# Attenuverting_mixer_mutes.net
KiCad netlist of a schematic drawn in EAGLE
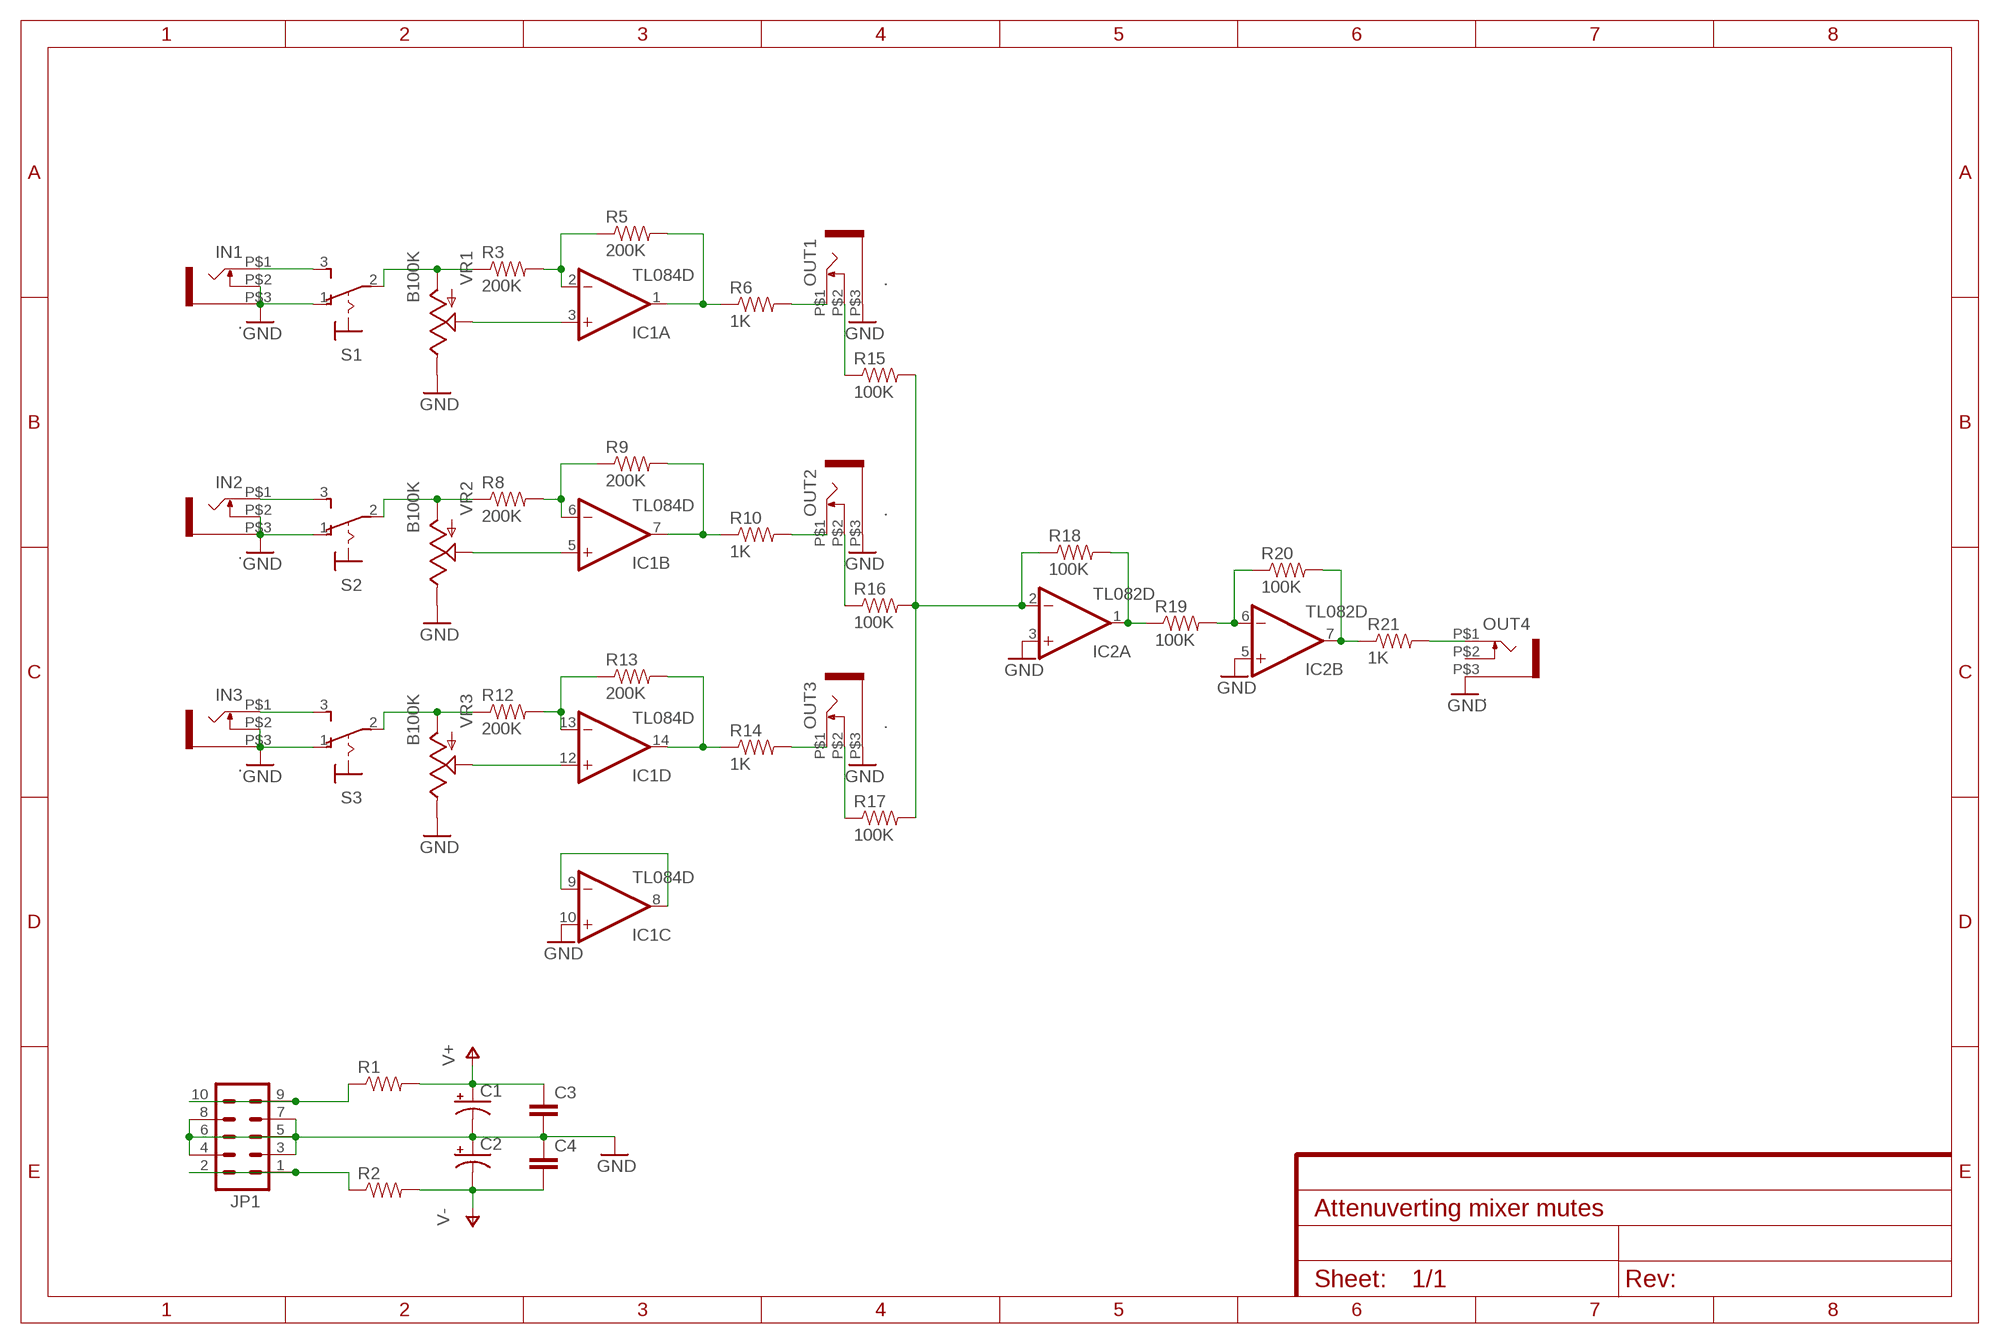
[diagram p0: schematic, sheet 1]

(export (version "E")
  (design (tool "Eeschema 10.0.6"))
  (components
    (comp (ref "C1")
      (value "CAP_POLD")
      (footprint "eagle-import:PANASONIC_D")
      (libsource (lib "eagle-import") (part "CAP_POLD"))
    )
    (comp (ref "C2")
      (value "CAP_POLD")
      (footprint "eagle-import:PANASONIC_D")
      (libsource (lib "eagle-import") (part "CAP_POLD"))
    )
    (comp (ref "C3")
      (value "CAP0603-CAP")
      (footprint "eagle-import:0603-CAP")
      (libsource (lib "eagle-import") (part "CAP0603-CAP"))
    )
    (comp (ref "C4")
      (value "CAP0603-CAP")
      (footprint "eagle-import:0603-CAP")
      (libsource (lib "eagle-import") (part "CAP0603-CAP"))
    )
    (comp (ref "IC1")
      (value "TL084D")
      (footprint "eagle-import:SO14")
      (libsource (lib "eagle-import") (part "TL084D"))
    )
    (comp (ref "IC2")
      (value "TL082D")
      (footprint "eagle-import:SO08")
      (libsource (lib "eagle-import") (part "TL082D"))
    )
    (comp (ref "IN1")
      (value ".")
      (footprint "eagle-import:WQP-PJ301M-12_JACK")
      (libsource (lib "eagle-import") (part "WQP-PJ301M-12_JACK"))
    )
    (comp (ref "IN2")
      (value ".")
      (footprint "eagle-import:WQP-PJ301M-12_JACK")
      (libsource (lib "eagle-import") (part "WQP-PJ301M-12_JACK"))
    )
    (comp (ref "IN3")
      (value ".")
      (footprint "eagle-import:WQP-PJ301M-12_JACK")
      (libsource (lib "eagle-import") (part "WQP-PJ301M-12_JACK"))
    )
    (comp (ref "JP1")
      (value "M05X2PTH")
      (footprint "eagle-import:AVR_ICSP")
      (libsource (lib "eagle-import") (part "M05X2PTH"))
    )
    (comp (ref "OUT1")
      (value ".")
      (footprint "eagle-import:WQP-PJ301M-12_JACK")
      (libsource (lib "eagle-import") (part "WQP-PJ301M-12_JACK"))
    )
    (comp (ref "OUT2")
      (value ".")
      (footprint "eagle-import:WQP-PJ301M-12_JACK")
      (libsource (lib "eagle-import") (part "WQP-PJ301M-12_JACK"))
    )
    (comp (ref "OUT3")
      (value ".")
      (footprint "eagle-import:WQP-PJ301M-12_JACK")
      (libsource (lib "eagle-import") (part "WQP-PJ301M-12_JACK"))
    )
    (comp (ref "OUT4")
      (value ".")
      (footprint "eagle-import:WQP-PJ301M-12_JACK")
      (libsource (lib "eagle-import") (part "WQP-PJ301M-12_JACK"))
    )
    (comp (ref "R1")
      (value "RESISTOR0805-RES")
      (footprint "eagle-import:0805")
      (libsource (lib "eagle-import") (part "SparkFun-Resistors_RESISTOR0805-RES"))
    )
    (comp (ref "R2")
      (value "RESISTOR0805-RES")
      (footprint "eagle-import:0805")
      (libsource (lib "eagle-import") (part "SparkFun-Resistors_RESISTOR0805-RES"))
    )
    (comp (ref "R3")
      (value "200K")
      (footprint "eagle-import:0603-RES")
      (libsource (lib "eagle-import") (part "RESISTOR0603-RES"))
    )
    (comp (ref "R5")
      (value "200K")
      (footprint "eagle-import:0603-RES")
      (libsource (lib "eagle-import") (part "RESISTOR0603-RES"))
    )
    (comp (ref "R6")
      (value "1K")
      (footprint "eagle-import:0603-RES")
      (libsource (lib "eagle-import") (part "RESISTOR0603-RES"))
    )
    (comp (ref "R8")
      (value "200K")
      (footprint "eagle-import:0603-RES")
      (libsource (lib "eagle-import") (part "RESISTOR0603-RES"))
    )
    (comp (ref "R9")
      (value "200K")
      (footprint "eagle-import:0603-RES")
      (libsource (lib "eagle-import") (part "RESISTOR0603-RES"))
    )
    (comp (ref "R10")
      (value "1K")
      (footprint "eagle-import:0603-RES")
      (libsource (lib "eagle-import") (part "RESISTOR0603-RES"))
    )
    (comp (ref "R12")
      (value "200K")
      (footprint "eagle-import:0603-RES")
      (libsource (lib "eagle-import") (part "RESISTOR0603-RES"))
    )
    (comp (ref "R13")
      (value "200K")
      (footprint "eagle-import:0603-RES")
      (libsource (lib "eagle-import") (part "RESISTOR0603-RES"))
    )
    (comp (ref "R14")
      (value "1K")
      (footprint "eagle-import:0603-RES")
      (libsource (lib "eagle-import") (part "RESISTOR0603-RES"))
    )
    (comp (ref "R15")
      (value "100K")
      (footprint "eagle-import:0603-RES")
      (libsource (lib "eagle-import") (part "RESISTOR0603-RES"))
    )
    (comp (ref "R16")
      (value "100K")
      (footprint "eagle-import:0603-RES")
      (libsource (lib "eagle-import") (part "RESISTOR0603-RES"))
    )
    (comp (ref "R17")
      (value "100K")
      (footprint "eagle-import:0603-RES")
      (libsource (lib "eagle-import") (part "RESISTOR0603-RES"))
    )
    (comp (ref "R18")
      (value "100K")
      (footprint "eagle-import:0603-RES")
      (libsource (lib "eagle-import") (part "RESISTOR0603-RES"))
    )
    (comp (ref "R19")
      (value "100K")
      (footprint "eagle-import:0603-RES")
      (libsource (lib "eagle-import") (part "RESISTOR0603-RES"))
    )
    (comp (ref "R20")
      (value "100K")
      (footprint "eagle-import:0603-RES")
      (libsource (lib "eagle-import") (part "RESISTOR0603-RES"))
    )
    (comp (ref "R21")
      (value "1K")
      (footprint "eagle-import:0603-RES")
      (libsource (lib "eagle-import") (part "RESISTOR0603-RES"))
    )
    (comp (ref "S1")
      (value "M9040P")
      (footprint "eagle-import:M9040P")
      (libsource (lib "eagle-import") (part "M9040P"))
    )
    (comp (ref "S2")
      (value "M9040P")
      (footprint "eagle-import:M9040P")
      (libsource (lib "eagle-import") (part "M9040P"))
    )
    (comp (ref "S3")
      (value "M9040P")
      (footprint "eagle-import:M9040P")
      (libsource (lib "eagle-import") (part "M9040P"))
    )
    (comp (ref "VR1")
      (value "B100K")
      (footprint "eagle-import:ALPS_POT")
      (libsource (lib "eagle-import") (part "POT"))
    )
    (comp (ref "VR2")
      (value "B100K")
      (footprint "eagle-import:ALPS_POT")
      (libsource (lib "eagle-import") (part "POT"))
    )
    (comp (ref "VR3")
      (value "B100K")
      (footprint "eagle-import:ALPS_POT")
      (libsource (lib "eagle-import") (part "POT"))
    )
  )
  (nets
    (net (code "1") (name "GND") (class "Default")
      (node (ref "C1") (pin "-") (pinfunction "-_-") (pintype "passive"))
      (node (ref "C2") (pin "+") (pinfunction "+_+") (pintype "passive"))
      (node (ref "C3") (pin "2") (pinfunction "2_2") (pintype "passive"))
      (node (ref "C4") (pin "1") (pinfunction "1_1") (pintype "passive"))
      (node (ref "IC1") (pin "10") (pinfunction "+IN_10") (pintype "input"))
      (node (ref "IC2") (pin "3") (pinfunction "+IN_3") (pintype "input"))
      (node (ref "IC2") (pin "5") (pinfunction "+IN_5") (pintype "input"))
      (node (ref "IN1") (pin "P$2") (pinfunction "3_P$2") (pintype "passive"))
      (node (ref "IN1") (pin "P$3") (pinfunction "1_P$3") (pintype "passive"))
      (node (ref "IN2") (pin "P$2") (pinfunction "3_P$2") (pintype "passive"))
      (node (ref "IN2") (pin "P$3") (pinfunction "1_P$3") (pintype "passive"))
      (node (ref "IN3") (pin "P$2") (pinfunction "3_P$2") (pintype "passive"))
      (node (ref "IN3") (pin "P$3") (pinfunction "1_P$3") (pintype "passive"))
      (node (ref "JP1") (pin "3") (pinfunction "3_3") (pintype "passive"))
      (node (ref "JP1") (pin "4") (pinfunction "4_4") (pintype "passive"))
      (node (ref "JP1") (pin "5") (pinfunction "5_5") (pintype "passive"))
      (node (ref "JP1") (pin "6") (pinfunction "6_6") (pintype "passive"))
      (node (ref "JP1") (pin "7") (pinfunction "7_7") (pintype "passive"))
      (node (ref "JP1") (pin "8") (pinfunction "8_8") (pintype "passive"))
      (node (ref "OUT1") (pin "P$3") (pinfunction "1_P$3") (pintype "passive"))
      (node (ref "OUT2") (pin "P$3") (pinfunction "1_P$3") (pintype "passive"))
      (node (ref "OUT3") (pin "P$3") (pinfunction "1_P$3") (pintype "passive"))
      (node (ref "OUT4") (pin "P$3") (pinfunction "1_P$3") (pintype "passive"))
      (node (ref "S1") (pin "1") (pinfunction "O_1") (pintype "passive"))
      (node (ref "S2") (pin "1") (pinfunction "O_1") (pintype "passive"))
      (node (ref "S3") (pin "1") (pinfunction "O_1") (pintype "passive"))
      (node (ref "VR1") (pin "P$1") (pinfunction "E_P$1") (pintype "passive"))
      (node (ref "VR2") (pin "P$1") (pinfunction "E_P$1") (pintype "passive"))
      (node (ref "VR3") (pin "P$1") (pinfunction "E_P$1") (pintype "passive"))
    )
    (net (code "2") (name "Net-(IC1A-+IN)") (class "Default")
      (node (ref "IC1") (pin "3") (pinfunction "+IN_3") (pintype "input"))
      (node (ref "VR1") (pin "P$2") (pinfunction "S_P$2") (pintype "passive"))
    )
    (net (code "3") (name "Net-(IC1A--IN)") (class "Default")
      (node (ref "IC1") (pin "2") (pinfunction "-IN_2") (pintype "input"))
      (node (ref "R3") (pin "2") (pinfunction "2_2") (pintype "passive"))
      (node (ref "R5") (pin "1") (pinfunction "1_1") (pintype "passive"))
    )
    (net (code "4") (name "Net-(IC1A-OUT)") (class "Default")
      (node (ref "IC1") (pin "1") (pinfunction "OUT_1") (pintype "output"))
      (node (ref "R5") (pin "2") (pinfunction "2_2") (pintype "passive"))
      (node (ref "R6") (pin "1") (pinfunction "1_1") (pintype "passive"))
    )
    (net (code "5") (name "Net-(IC1B-+IN)") (class "Default")
      (node (ref "IC1") (pin "5") (pinfunction "+IN_5") (pintype "input"))
      (node (ref "VR2") (pin "P$2") (pinfunction "S_P$2") (pintype "passive"))
    )
    (net (code "6") (name "Net-(IC1B--IN)") (class "Default")
      (node (ref "IC1") (pin "6") (pinfunction "-IN_6") (pintype "input"))
      (node (ref "R8") (pin "2") (pinfunction "2_2") (pintype "passive"))
      (node (ref "R9") (pin "1") (pinfunction "1_1") (pintype "passive"))
    )
    (net (code "7") (name "Net-(IC1B-OUT)") (class "Default")
      (node (ref "IC1") (pin "7") (pinfunction "OUT_7") (pintype "output"))
      (node (ref "R10") (pin "1") (pinfunction "1_1") (pintype "passive"))
      (node (ref "R9") (pin "2") (pinfunction "2_2") (pintype "passive"))
    )
    (net (code "8") (name "Net-(IC1C--IN)") (class "Default")
      (node (ref "IC1") (pin "8") (pinfunction "OUT_8") (pintype "output"))
      (node (ref "IC1") (pin "9") (pinfunction "-IN_9") (pintype "input"))
    )
    (net (code "9") (name "Net-(IC1D-+IN)") (class "Default")
      (node (ref "IC1") (pin "12") (pinfunction "+IN_12") (pintype "input"))
      (node (ref "VR3") (pin "P$2") (pinfunction "S_P$2") (pintype "passive"))
    )
    (net (code "10") (name "Net-(IC1D--IN)") (class "Default")
      (node (ref "IC1") (pin "13") (pinfunction "-IN_13") (pintype "input"))
      (node (ref "R12") (pin "2") (pinfunction "2_2") (pintype "passive"))
      (node (ref "R13") (pin "1") (pinfunction "1_1") (pintype "passive"))
    )
    (net (code "11") (name "Net-(IC1D-OUT)") (class "Default")
      (node (ref "IC1") (pin "14") (pinfunction "OUT_14") (pintype "output"))
      (node (ref "R13") (pin "2") (pinfunction "2_2") (pintype "passive"))
      (node (ref "R14") (pin "1") (pinfunction "1_1") (pintype "passive"))
    )
    (net (code "12") (name "Net-(IC2A--IN)") (class "Default")
      (node (ref "IC2") (pin "2") (pinfunction "-IN_2") (pintype "input"))
      (node (ref "R15") (pin "2") (pinfunction "2_2") (pintype "passive"))
      (node (ref "R16") (pin "2") (pinfunction "2_2") (pintype "passive"))
      (node (ref "R17") (pin "2") (pinfunction "2_2") (pintype "passive"))
      (node (ref "R18") (pin "1") (pinfunction "1_1") (pintype "passive"))
    )
    (net (code "13") (name "Net-(IC2A-OUT)") (class "Default")
      (node (ref "IC2") (pin "1") (pinfunction "OUT_1") (pintype "output"))
      (node (ref "R18") (pin "2") (pinfunction "2_2") (pintype "passive"))
      (node (ref "R19") (pin "1") (pinfunction "1_1") (pintype "passive"))
    )
    (net (code "14") (name "Net-(IC2B--IN)") (class "Default")
      (node (ref "IC2") (pin "6") (pinfunction "-IN_6") (pintype "input"))
      (node (ref "R19") (pin "2") (pinfunction "2_2") (pintype "passive"))
      (node (ref "R20") (pin "1") (pinfunction "1_1") (pintype "passive"))
    )
    (net (code "15") (name "Net-(IC2B-OUT)") (class "Default")
      (node (ref "IC2") (pin "7") (pinfunction "OUT_7") (pintype "output"))
      (node (ref "R20") (pin "2") (pinfunction "2_2") (pintype "passive"))
      (node (ref "R21") (pin "1") (pinfunction "1_1") (pintype "passive"))
    )
    (net (code "16") (name "Net-(IN1-2)") (class "Default")
      (node (ref "IN1") (pin "P$1") (pinfunction "2_P$1") (pintype "passive"))
      (node (ref "S1") (pin "3") (pinfunction "S_3") (pintype "passive"))
    )
    (net (code "17") (name "Net-(IN2-2)") (class "Default")
      (node (ref "IN2") (pin "P$1") (pinfunction "2_P$1") (pintype "passive"))
      (node (ref "S2") (pin "3") (pinfunction "S_3") (pintype "passive"))
    )
    (net (code "18") (name "Net-(IN3-2)") (class "Default")
      (node (ref "IN3") (pin "P$1") (pinfunction "2_P$1") (pintype "passive"))
      (node (ref "S3") (pin "3") (pinfunction "S_3") (pintype "passive"))
    )
    (net (code "19") (name "Net-(JP1-Pad1)") (class "Default")
      (node (ref "JP1") (pin "1") (pinfunction "1_1") (pintype "passive"))
      (node (ref "JP1") (pin "2") (pinfunction "2_2") (pintype "passive"))
      (node (ref "R2") (pin "1") (pinfunction "1_1") (pintype "passive"))
    )
    (net (code "20") (name "Net-(JP1-Pad10)") (class "Default")
      (node (ref "JP1") (pin "10") (pinfunction "10_10") (pintype "passive"))
      (node (ref "JP1") (pin "9") (pinfunction "9_9") (pintype "passive"))
      (node (ref "R1") (pin "1") (pinfunction "1_1") (pintype "passive"))
    )
    (net (code "21") (name "Net-(OUT1-2)") (class "Default")
      (node (ref "OUT1") (pin "P$1") (pinfunction "2_P$1") (pintype "passive"))
      (node (ref "R6") (pin "2") (pinfunction "2_2") (pintype "passive"))
    )
    (net (code "22") (name "Net-(OUT1-3)") (class "Default")
      (node (ref "OUT1") (pin "P$2") (pinfunction "3_P$2") (pintype "passive"))
      (node (ref "R15") (pin "1") (pinfunction "1_1") (pintype "passive"))
    )
    (net (code "23") (name "Net-(OUT2-2)") (class "Default")
      (node (ref "OUT2") (pin "P$1") (pinfunction "2_P$1") (pintype "passive"))
      (node (ref "R10") (pin "2") (pinfunction "2_2") (pintype "passive"))
    )
    (net (code "24") (name "Net-(OUT2-3)") (class "Default")
      (node (ref "OUT2") (pin "P$2") (pinfunction "3_P$2") (pintype "passive"))
      (node (ref "R16") (pin "1") (pinfunction "1_1") (pintype "passive"))
    )
    (net (code "25") (name "Net-(OUT3-2)") (class "Default")
      (node (ref "OUT3") (pin "P$1") (pinfunction "2_P$1") (pintype "passive"))
      (node (ref "R14") (pin "2") (pinfunction "2_2") (pintype "passive"))
    )
    (net (code "26") (name "Net-(OUT3-3)") (class "Default")
      (node (ref "OUT3") (pin "P$2") (pinfunction "3_P$2") (pintype "passive"))
      (node (ref "R17") (pin "1") (pinfunction "1_1") (pintype "passive"))
    )
    (net (code "27") (name "Net-(OUT4-2)") (class "Default")
      (node (ref "OUT4") (pin "P$1") (pinfunction "2_P$1") (pintype "passive"))
      (node (ref "R21") (pin "2") (pinfunction "2_2") (pintype "passive"))
    )
    (net (code "28") (name "Net-(S1-P)") (class "Default")
      (node (ref "R3") (pin "1") (pinfunction "1_1") (pintype "passive"))
      (node (ref "S1") (pin "2") (pinfunction "P_2") (pintype "passive"))
      (node (ref "VR1") (pin "P$3") (pinfunction "A_P$3") (pintype "passive"))
    )
    (net (code "29") (name "Net-(S2-P)") (class "Default")
      (node (ref "R8") (pin "1") (pinfunction "1_1") (pintype "passive"))
      (node (ref "S2") (pin "2") (pinfunction "P_2") (pintype "passive"))
      (node (ref "VR2") (pin "P$3") (pinfunction "A_P$3") (pintype "passive"))
    )
    (net (code "30") (name "Net-(S3-P)") (class "Default")
      (node (ref "R12") (pin "1") (pinfunction "1_1") (pintype "passive"))
      (node (ref "S3") (pin "2") (pinfunction "P_2") (pintype "passive"))
      (node (ref "VR3") (pin "P$3") (pinfunction "A_P$3") (pintype "passive"))
    )
    (net (code "31") (name "V+") (class "Default")
      (node (ref "C1") (pin "+") (pinfunction "+_+") (pintype "passive"))
      (node (ref "C3") (pin "1") (pinfunction "1_1") (pintype "passive"))
      (node (ref "R1") (pin "2") (pinfunction "2_2") (pintype "passive"))
    )
    (net (code "32") (name "V-") (class "Default")
      (node (ref "C2") (pin "-") (pinfunction "-_-") (pintype "passive"))
      (node (ref "C4") (pin "2") (pinfunction "2_2") (pintype "passive"))
      (node (ref "R2") (pin "2") (pinfunction "2_2") (pintype "passive"))
    )
    (net (code "33") (name "unconnected-(OUT4-3-PadP$2)") (class "Default")
      (node (ref "OUT4") (pin "P$2") (pinfunction "3_P$2") (pintype "passive"))
    )
  )
)
